# teensy_relay_controller.net
KiCad netlist of a schematic drawn in EAGLE
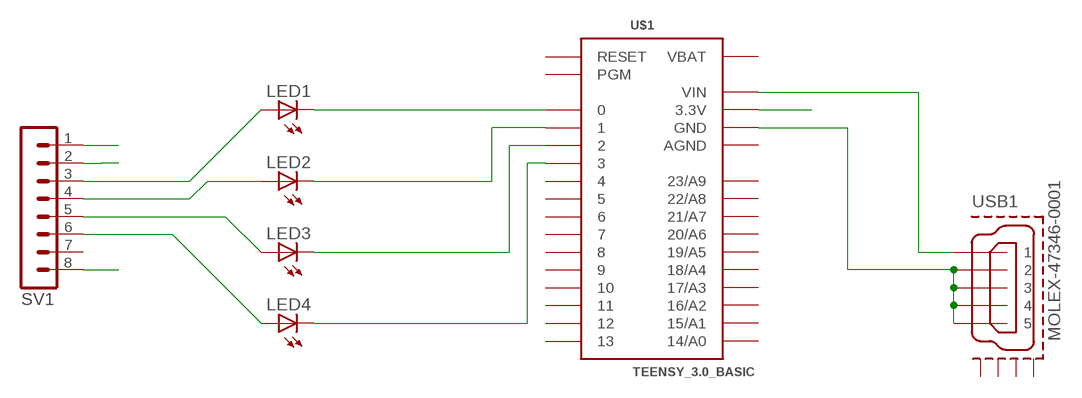
[diagram p0: schematic, sheet 1]

(export (version "E")
  (design (tool "Eeschema 10.0.6"))
  (components
    (comp (ref "LED1")
      (value "LED5MM")
      (footprint "eagle-import:LED5MM")
      (libsource (lib "eagle-import") (part "LED5MM"))
    )
    (comp (ref "LED2")
      (value "LED5MM")
      (footprint "eagle-import:LED5MM")
      (libsource (lib "eagle-import") (part "LED5MM"))
    )
    (comp (ref "LED3")
      (value "LED5MM")
      (footprint "eagle-import:LED5MM")
      (libsource (lib "eagle-import") (part "LED5MM"))
    )
    (comp (ref "LED4")
      (value "LED5MM")
      (footprint "eagle-import:LED5MM")
      (libsource (lib "eagle-import") (part "LED5MM"))
    )
    (comp (ref "SV1")
      (value "MA08-1")
      (footprint "eagle-import:MA08-1")
      (libsource (lib "eagle-import") (part "MA08-1"))
    )
    (comp (ref "U$1")
      (value "TEENSY_3.0_BASIC")
      (footprint "eagle-import:TEENSY_3.0_BASIC")
      (libsource (lib "eagle-import") (part "TEENSY_3.0_BASIC"))
    )
    (comp (ref "USB1")
      (value "MOLEX-47346-0001")
      (footprint "eagle-import:MOLEX-47364-0001")
      (libsource (lib "eagle-import") (part "MOLEX-47346-0001"))
    )
  )
  (nets
    (net (code "1") (name "/3.3V_VCC") (class "Default")
      (node (ref "SV1") (pin "2") (pinfunction "2_2") (pintype "passive"))
      (node (ref "U$1") (pin "3.3V") (pinfunction "3.3V_3.3V") (pintype "power_in"))
      (node (ref "U$1") (pin "3.3V1") (pinfunction "3.3V_3.3V1") (pintype "power_in"))
    )
    (net (code "2") (name "/5V_VCC") (class "Default")
      (node (ref "SV1") (pin "1") (pinfunction "1_1") (pintype "passive"))
      (node (ref "U$1") (pin "VIN") (pinfunction "VIN_VIN") (pintype "power_in"))
      (node (ref "USB1") (pin "1") (pinfunction "1_1") (pintype "input"))
    )
    (net (code "3") (name "/AGND") (class "Default")
      (node (ref "U$1") (pin "AGND") (pinfunction "AGND_AGND") (pintype "power_in"))
    )
    (net (code "4") (name "/GND") (class "Default")
      (node (ref "SV1") (pin "8") (pinfunction "8_8") (pintype "passive"))
      (node (ref "U$1") (pin "GND") (pinfunction "GND_GND") (pintype "power_in"))
      (node (ref "U$1") (pin "GND1") (pinfunction "GND_GND1") (pintype "power_in"))
      (node (ref "USB1") (pin "2") (pinfunction "2_2") (pintype "input"))
      (node (ref "USB1") (pin "3") (pinfunction "3_3") (pintype "input"))
      (node (ref "USB1") (pin "4") (pinfunction "4_4") (pintype "input"))
      (node (ref "USB1") (pin "5") (pinfunction "5_5") (pintype "input"))
    )
    (net (code "5") (name "/VBAT") (class "Default")
      (node (ref "U$1") (pin "VBAT") (pinfunction "VBAT_VBAT") (pintype "power_in"))
    )
    (net (code "6") (name "Net-(LED1-C)") (class "Default")
      (node (ref "LED1") (pin "K") (pinfunction "C_K") (pintype "passive"))
      (node (ref "U$1") (pin "0") (pinfunction "0_0") (pintype "bidirectional"))
    )
    (net (code "7") (name "Net-(LED1-PadA)") (class "Default")
      (node (ref "LED1") (pin "A") (pinfunction "A_A") (pintype "passive"))
      (node (ref "SV1") (pin "3") (pinfunction "3_3") (pintype "passive"))
    )
    (net (code "8") (name "Net-(LED2-C)") (class "Default")
      (node (ref "LED2") (pin "K") (pinfunction "C_K") (pintype "passive"))
      (node (ref "U$1") (pin "1") (pinfunction "1_1") (pintype "bidirectional"))
    )
    (net (code "9") (name "Net-(LED2-PadA)") (class "Default")
      (node (ref "LED2") (pin "A") (pinfunction "A_A") (pintype "passive"))
      (node (ref "SV1") (pin "4") (pinfunction "4_4") (pintype "passive"))
    )
    (net (code "10") (name "Net-(LED3-C)") (class "Default")
      (node (ref "LED3") (pin "K") (pinfunction "C_K") (pintype "passive"))
      (node (ref "U$1") (pin "2") (pinfunction "2_2") (pintype "bidirectional"))
    )
    (net (code "11") (name "Net-(LED3-PadA)") (class "Default")
      (node (ref "LED3") (pin "A") (pinfunction "A_A") (pintype "passive"))
      (node (ref "SV1") (pin "5") (pinfunction "5_5") (pintype "passive"))
    )
    (net (code "12") (name "Net-(LED4-C)") (class "Default")
      (node (ref "LED4") (pin "K") (pinfunction "C_K") (pintype "passive"))
      (node (ref "U$1") (pin "3") (pinfunction "3_3") (pintype "bidirectional"))
    )
    (net (code "13") (name "Net-(LED4-PadA)") (class "Default")
      (node (ref "LED4") (pin "A") (pinfunction "A_A") (pintype "passive"))
      (node (ref "SV1") (pin "6") (pinfunction "6_6") (pintype "passive"))
    )
    (net (code "14") (name "unconnected-(SV1-Pad7)") (class "Default")
      (node (ref "SV1") (pin "7") (pinfunction "7_7") (pintype "passive"))
    )
    (net (code "15") (name "unconnected-(U$1-Pad4)") (class "Default")
      (node (ref "U$1") (pin "4") (pinfunction "4_4") (pintype "bidirectional"))
    )
    (net (code "16") (name "unconnected-(U$1-Pad5)") (class "Default")
      (node (ref "U$1") (pin "5") (pinfunction "5_5") (pintype "bidirectional"))
    )
    (net (code "17") (name "unconnected-(U$1-Pad6)") (class "Default")
      (node (ref "U$1") (pin "6") (pinfunction "6_6") (pintype "bidirectional"))
    )
    (net (code "18") (name "unconnected-(U$1-Pad7)") (class "Default")
      (node (ref "U$1") (pin "7") (pinfunction "7_7") (pintype "bidirectional"))
    )
    (net (code "19") (name "unconnected-(U$1-Pad8)") (class "Default")
      (node (ref "U$1") (pin "8") (pinfunction "8_8") (pintype "bidirectional"))
    )
    (net (code "20") (name "unconnected-(U$1-Pad9)") (class "Default")
      (node (ref "U$1") (pin "9") (pinfunction "9_9") (pintype "bidirectional"))
    )
    (net (code "21") (name "unconnected-(U$1-Pad10)") (class "Default")
      (node (ref "U$1") (pin "10") (pinfunction "10_10") (pintype "bidirectional"))
    )
    (net (code "22") (name "unconnected-(U$1-Pad11)") (class "Default")
      (node (ref "U$1") (pin "11") (pinfunction "11_11") (pintype "bidirectional"))
    )
    (net (code "23") (name "unconnected-(U$1-Pad12)") (class "Default")
      (node (ref "U$1") (pin "12") (pinfunction "12_12") (pintype "bidirectional"))
    )
    (net (code "24") (name "unconnected-(U$1-Pad13)") (class "Default")
      (node (ref "U$1") (pin "13") (pinfunction "13_13") (pintype "bidirectional"))
    )
    (net (code "25") (name "unconnected-(U$1-Pad14{slash}A0)") (class "Default")
      (node (ref "U$1") (pin "14/A0") (pinfunction "14/A0_14/A0") (pintype "bidirectional"))
    )
    (net (code "26") (name "unconnected-(U$1-Pad15{slash}A1)") (class "Default")
      (node (ref "U$1") (pin "15/A1") (pinfunction "15/A1_15/A1") (pintype "bidirectional"))
    )
    (net (code "27") (name "unconnected-(U$1-Pad16{slash}A2)") (class "Default")
      (node (ref "U$1") (pin "16/A2") (pinfunction "16/A2_16/A2") (pintype "bidirectional"))
    )
    (net (code "28") (name "unconnected-(U$1-Pad17{slash}A3)") (class "Default")
      (node (ref "U$1") (pin "17/A3") (pinfunction "17/A3_17/A3") (pintype "bidirectional"))
    )
    (net (code "29") (name "unconnected-(U$1-Pad18{slash}A4)") (class "Default")
      (node (ref "U$1") (pin "18/A4") (pinfunction "18/A4_18/A4") (pintype "bidirectional"))
    )
    (net (code "30") (name "unconnected-(U$1-Pad19{slash}A5)") (class "Default")
      (node (ref "U$1") (pin "19/A5") (pinfunction "19/A5_19/A5") (pintype "bidirectional"))
    )
    (net (code "31") (name "unconnected-(U$1-Pad20{slash}A6)") (class "Default")
      (node (ref "U$1") (pin "20/A6") (pinfunction "20/A6_20/A6") (pintype "bidirectional"))
    )
    (net (code "32") (name "unconnected-(U$1-Pad21{slash}A7)") (class "Default")
      (node (ref "U$1") (pin "21/A7") (pinfunction "21/A7_21/A7") (pintype "bidirectional"))
    )
    (net (code "33") (name "unconnected-(U$1-Pad22{slash}A8)") (class "Default")
      (node (ref "U$1") (pin "22/A8") (pinfunction "22/A8_22/A8") (pintype "bidirectional"))
    )
    (net (code "34") (name "unconnected-(U$1-Pad23{slash}A9)") (class "Default")
      (node (ref "U$1") (pin "23/A9") (pinfunction "23/A9_23/A9") (pintype "bidirectional"))
    )
    (net (code "35") (name "unconnected-(U$1-PadPGM)") (class "Default")
      (node (ref "U$1") (pin "PGM") (pinfunction "PGM_PGM") (pintype "bidirectional"))
    )
    (net (code "36") (name "unconnected-(U$1-PadRESET)") (class "Default")
      (node (ref "U$1") (pin "RESET") (pinfunction "RESET_RESET") (pintype "bidirectional"))
    )
    (net (code "37") (name "unconnected-(USB1-PadGND1)") (class "Default")
      (node (ref "USB1") (pin "GND1") (pinfunction "GND1_GND1") (pintype "bidirectional"))
    )
    (net (code "38") (name "unconnected-(USB1-PadGND2)") (class "Default")
      (node (ref "USB1") (pin "GND2") (pinfunction "GND2_GND2") (pintype "bidirectional"))
    )
    (net (code "39") (name "unconnected-(USB1-PadGND3)") (class "Default")
      (node (ref "USB1") (pin "GND3") (pinfunction "GND3_GND3") (pintype "bidirectional"))
    )
    (net (code "40") (name "unconnected-(USB1-PadGND4)") (class "Default")
      (node (ref "USB1") (pin "GND4") (pinfunction "GND4_GND4") (pintype "bidirectional"))
    )
  )
)
